# AC-DC.net
KiCad netlist of a schematic drawn in Altium Designer
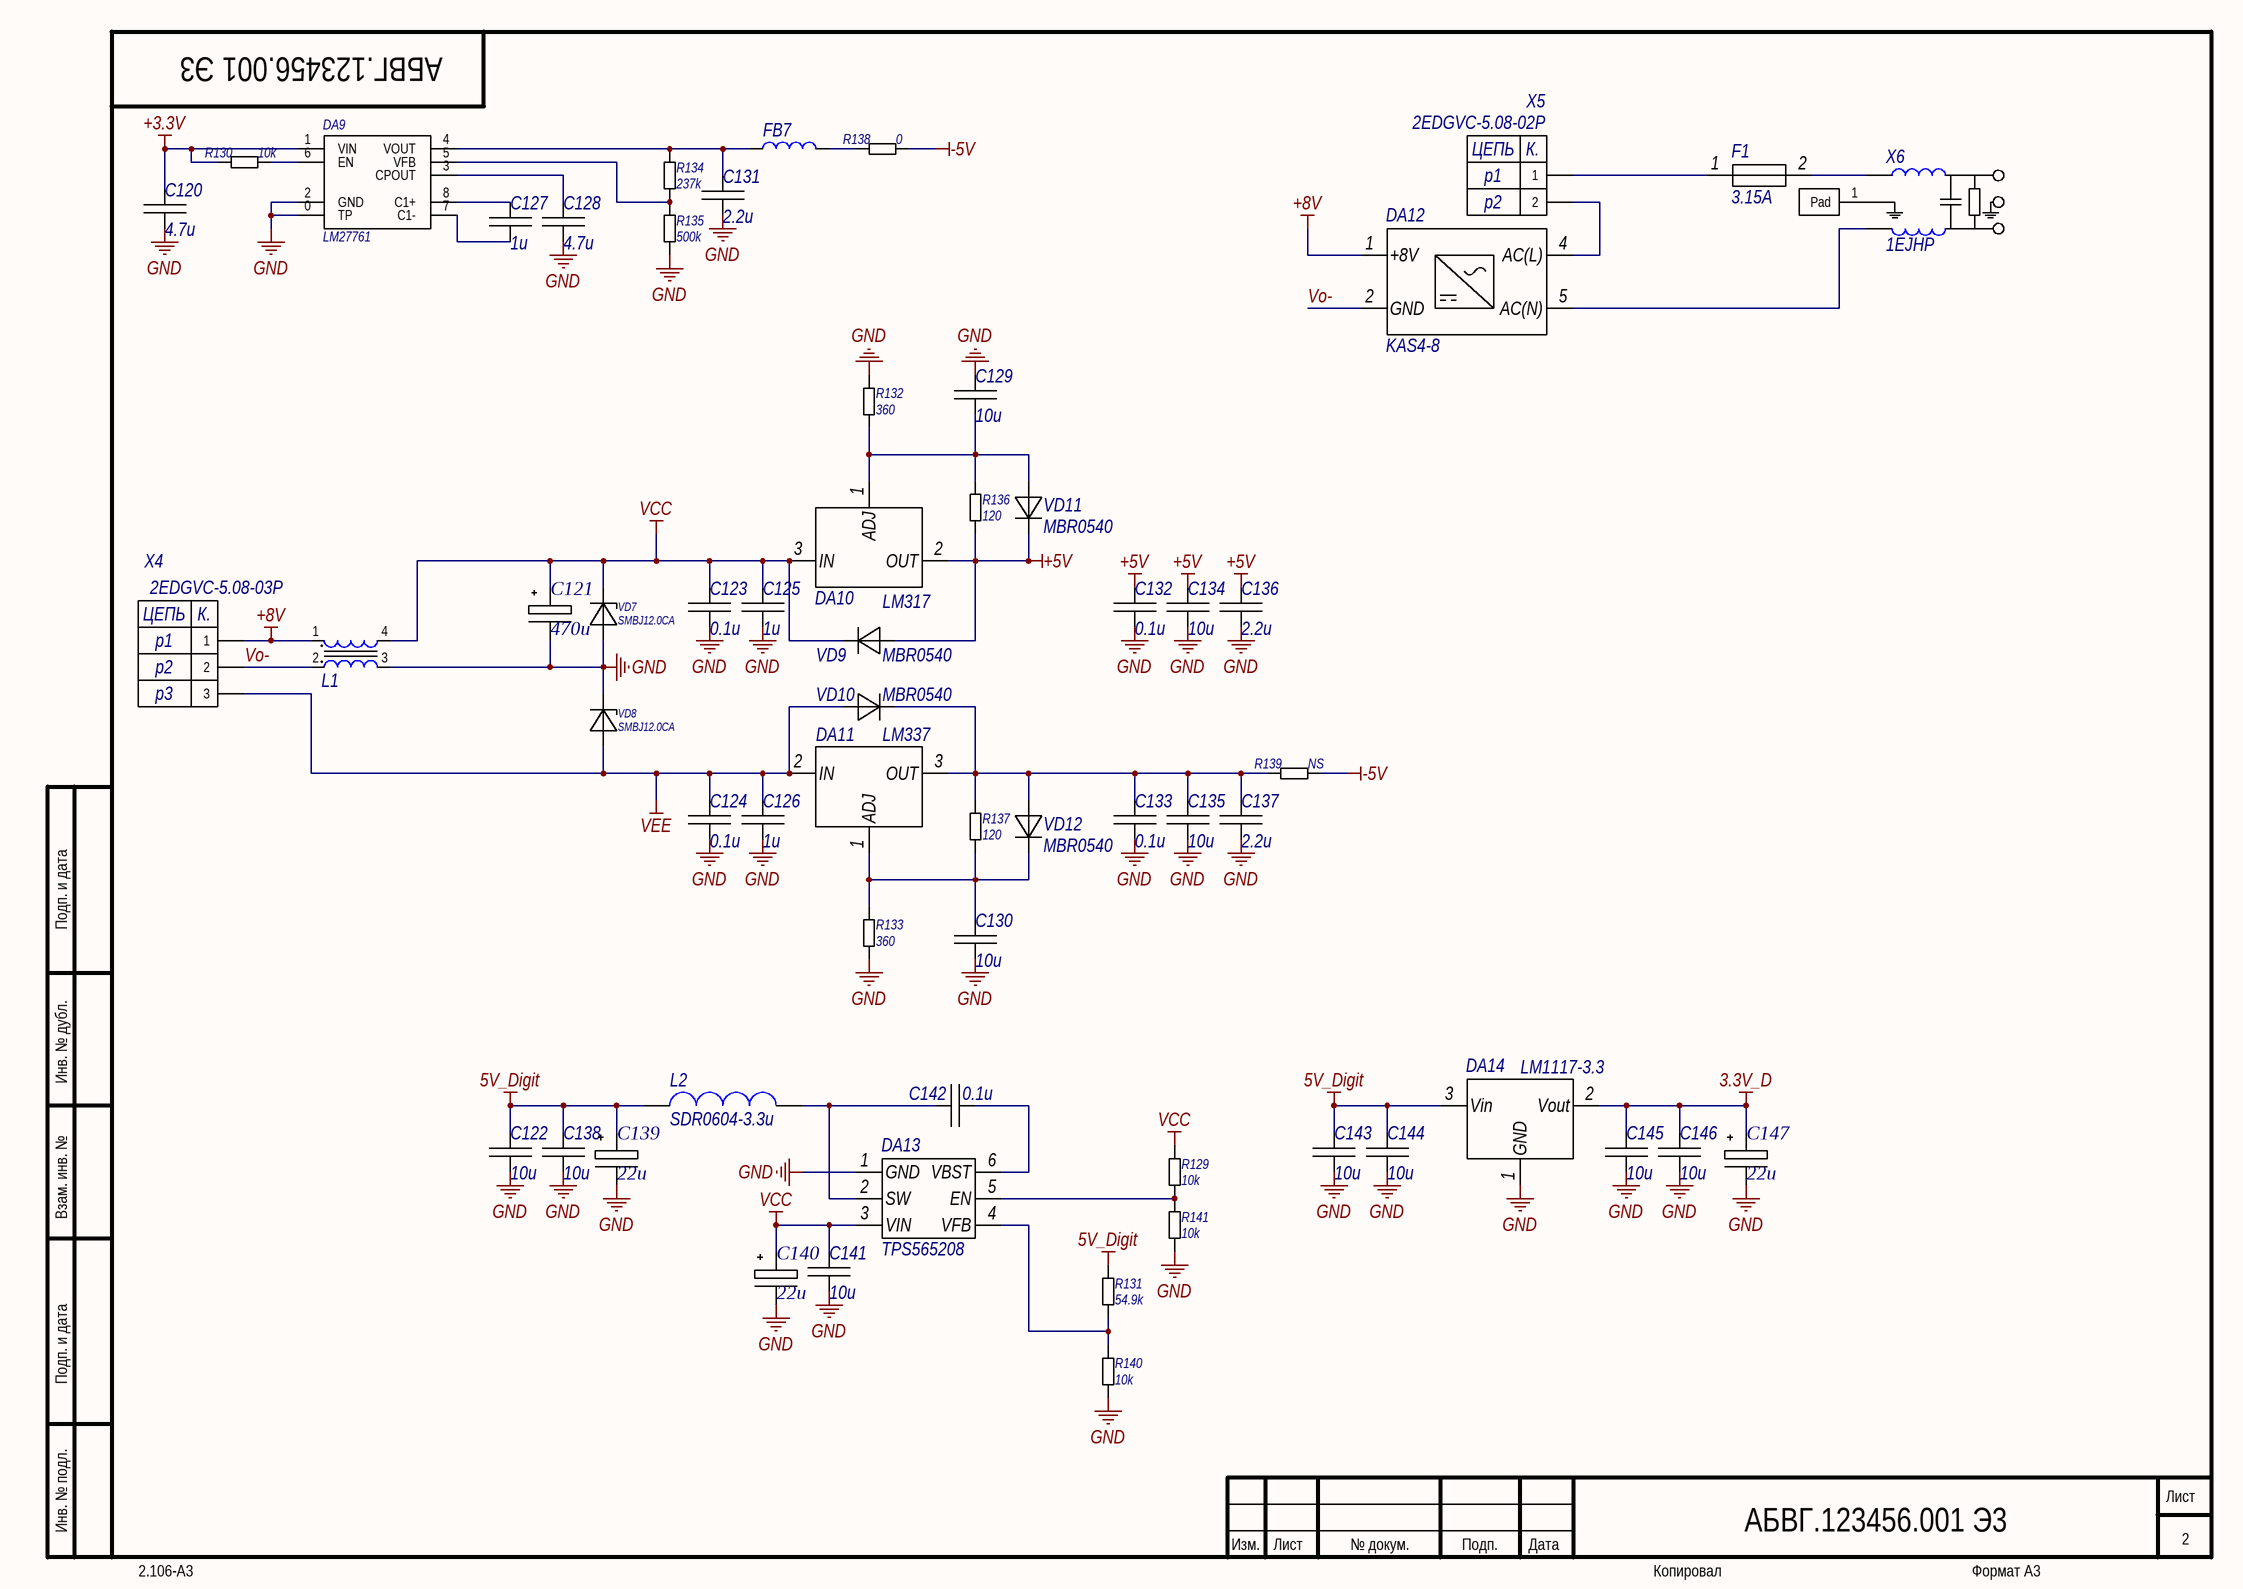
[diagram p0: AC-DC.SchDoc]

(export (version "E")
  (design (tool "Eeschema 10.0.6"))
  (components
    (comp (ref "C120")
      (value "4.7u")
      (footprint "C0805")
      (libsource (lib "ComLib") (part "Capacitor Ceramic SMD"))
    )
    (comp (ref "C121")
      (value "470u")
      (footprint "C1717")
      (libsource (lib "ComLib") (part "Capacitor Electrolytic"))
    )
    (comp (ref "C122")
      (value "10u")
      (footprint "C1206")
      (libsource (lib "ComLib") (part "Capacitor Ceramic SMD"))
    )
    (comp (ref "C123")
      (value "0.1u")
      (footprint "C1206")
      (libsource (lib "ComLib") (part "Capacitor Ceramic SMD"))
    )
    (comp (ref "C124")
      (value "0.1u")
      (footprint "C1206")
      (libsource (lib "ComLib") (part "Capacitor Ceramic SMD"))
    )
    (comp (ref "C125")
      (value "1u")
      (footprint "C1206")
      (libsource (lib "ComLib") (part "Capacitor Ceramic SMD"))
    )
    (comp (ref "C126")
      (value "1u")
      (footprint "C1206")
      (libsource (lib "ComLib") (part "Capacitor Ceramic SMD"))
    )
    (comp (ref "C127")
      (value "1u")
      (footprint "C0805")
      (libsource (lib "ComLib") (part "Capacitor Ceramic SMD"))
    )
    (comp (ref "C128")
      (value "4.7u")
      (footprint "C0805")
      (libsource (lib "ComLib") (part "Capacitor Ceramic SMD"))
    )
    (comp (ref "C129")
      (value "10u")
      (footprint "C1206")
      (libsource (lib "ComLib") (part "Capacitor Ceramic SMD"))
    )
    (comp (ref "C130")
      (value "10u")
      (footprint "C1206")
      (libsource (lib "ComLib") (part "Capacitor Ceramic SMD"))
    )
    (comp (ref "C131")
      (value "2.2u")
      (footprint "C0805")
      (libsource (lib "ComLib") (part "Capacitor Ceramic SMD"))
    )
    (comp (ref "C132")
      (value "0.1u")
      (footprint "C1206")
      (libsource (lib "ComLib") (part "Capacitor Ceramic SMD"))
    )
    (comp (ref "C133")
      (value "0.1u")
      (footprint "C1206")
      (libsource (lib "ComLib") (part "Capacitor Ceramic SMD"))
    )
    (comp (ref "C134")
      (value "10u")
      (footprint "C1206")
      (libsource (lib "ComLib") (part "Capacitor Ceramic SMD"))
    )
    (comp (ref "C135")
      (value "10u")
      (footprint "C1206")
      (libsource (lib "ComLib") (part "Capacitor Ceramic SMD"))
    )
    (comp (ref "C136")
      (value "2.2u")
      (footprint "C1206")
      (libsource (lib "ComLib") (part "Capacitor Ceramic SMD"))
    )
    (comp (ref "C137")
      (value "2.2u")
      (footprint "C1206")
      (libsource (lib "ComLib") (part "Capacitor Ceramic SMD"))
    )
    (comp (ref "C138")
      (value "10u")
      (footprint "C1206")
      (libsource (lib "ComLib") (part "Capacitor Ceramic SMD"))
    )
    (comp (ref "C139")
      (value "22u")
      (footprint "C0605")
      (libsource (lib "ComLib") (part "Capacitor Electrolytic"))
    )
    (comp (ref "C140")
      (value "22u")
      (footprint "C0605")
      (libsource (lib "ComLib") (part "Capacitor Electrolytic"))
    )
    (comp (ref "C141")
      (value "10u")
      (footprint "C1206")
      (libsource (lib "ComLib") (part "Capacitor Ceramic SMD"))
    )
    (comp (ref "C142")
      (value "0.1u")
      (footprint "C1206")
      (libsource (lib "ComLib") (part "Capacitor Ceramic SMD"))
    )
    (comp (ref "C143")
      (value "10u")
      (footprint "C1206")
      (libsource (lib "ComLib") (part "Capacitor Ceramic SMD"))
    )
    (comp (ref "C144")
      (value "10u")
      (footprint "C1206")
      (libsource (lib "ComLib") (part "Capacitor Ceramic SMD"))
    )
    (comp (ref "C145")
      (value "10u")
      (footprint "C1206")
      (libsource (lib "ComLib") (part "Capacitor Ceramic SMD"))
    )
    (comp (ref "C146")
      (value "10u")
      (footprint "C1206")
      (libsource (lib "ComLib") (part "Capacitor Ceramic SMD"))
    )
    (comp (ref "C147")
      (value "22u")
      (footprint "C0605")
      (libsource (lib "ComLib") (part "Capacitor Electrolytic"))
    )
    (comp (ref "DA9") (value "LM27761") (footprint "WSON-8") (libsource (lib "ComLib") (part "LM27761")))
    (comp (ref "DA10") (value "LM317") (footprint "D2PAK") (libsource (lib "Librio_TS") (part "LM317")))
    (comp (ref "DA11") (value "LM337") (footprint "D2PAK") (libsource (lib "Librio_TS") (part "LM337")))
    (comp (ref "DA12") (value "KAS4-8") (footprint "KAS4-8") (libsource (lib "ComLib") (part "KAS4-8")))
    (comp (ref "DA13")
      (value "TPS565208")
      (footprint "SOT23-6")
      (libsource (lib "ComLib") (part "TPS565208"))
    )
    (comp (ref "DA14")
      (value "LM1117-3.3")
      (footprint "DPAK - LM1117")
      (libsource (lib "Librio_TS") (part "LM1117"))
    )
    (comp (ref "F1") (value "3.15A") (footprint "5x20mm") (libsource (lib "ComLib") (part "FUSE_HOLDER")))
    (comp (ref "FB7")
      (value "MH1608-601Y")
      (footprint "L0603")
      (libsource (lib "ComLib") (part "Ferrite Bead"))
    )
    (comp (ref "L1")
      (value "744221")
      (footprint "WE-SL2 SMD")
      (libsource (lib "ComLib") (part "CommonModeChoke"))
    )
    (comp (ref "L2")
      (value "SDR0604-3.3u")
      (footprint "SDR0604")
      (libsource (lib "Librio_TS") (part "SDR0604"))
    )
    (comp (ref "P1") (value "PAD") (footprint "PAD") (libsource (lib "Librio_TS") (part "PAD")))
    (comp (ref "R129") (value "10k") (footprint "CR0805") (libsource (lib "ComLib") (part "Resistor SMD")))
    (comp (ref "R130") (value "10k") (footprint "CR0805") (libsource (lib "ComLib") (part "Resistor SMD")))
    (comp (ref "R131") (value "54.9k") (footprint "CR0805") (libsource (lib "ComLib") (part "Resistor SMD")))
    (comp (ref "R132") (value "360") (footprint "CR1206") (libsource (lib "ComLib") (part "Resistor SMD")))
    (comp (ref "R133") (value "360") (footprint "CR1206") (libsource (lib "ComLib") (part "Resistor SMD")))
    (comp (ref "R134") (value "237k") (footprint "CR0805") (libsource (lib "ComLib") (part "Resistor SMD")))
    (comp (ref "R135") (value "500k") (footprint "CR0805") (libsource (lib "ComLib") (part "Resistor SMD")))
    (comp (ref "R136") (value "120") (footprint "CR1206") (libsource (lib "ComLib") (part "Resistor SMD")))
    (comp (ref "R137") (value "120") (footprint "CR1206") (libsource (lib "ComLib") (part "Resistor SMD")))
    (comp (ref "R138") (value "0") (footprint "CR0805") (libsource (lib "ComLib") (part "Resistor SMD")))
    (comp (ref "R139") (value "NS") (footprint "CR0805") (libsource (lib "ComLib") (part "Resistor SMD")))
    (comp (ref "R140") (value "10k") (footprint "CR0805") (libsource (lib "ComLib") (part "Resistor SMD")))
    (comp (ref "R141") (value "10k") (footprint "CR0805") (libsource (lib "ComLib") (part "Resistor SMD")))
    (comp (ref "VD7")
      (value "SMBJ12.0CA")
      (footprint "DO-214AA")
      (libsource (lib "Librio_TS") (part "SMBJ5.0CA"))
    )
    (comp (ref "VD8")
      (value "SMBJ12.0CA")
      (footprint "DO-214AA")
      (libsource (lib "Librio_TS") (part "SMBJ5.0CA"))
    )
    (comp (ref "VD9") (value "MBR0540") (footprint "SOD123") (libsource (lib "ComLib") (part "Diode")))
    (comp (ref "VD10") (value "MBR0540") (footprint "SOD123") (libsource (lib "ComLib") (part "Diode")))
    (comp (ref "VD11") (value "MBR0540") (footprint "SOD123") (libsource (lib "ComLib") (part "Diode")))
    (comp (ref "VD12") (value "MBR0540") (footprint "SOD123") (libsource (lib "ComLib") (part "Diode")))
    (comp (ref "X4")
      (value "2EDGVC-5.08-03P")
      (footprint "2EDGVC-5.08-03P")
      (fields
        (field (name "ALTIUM_UNNAMED_1") "p1")
        (field (name "ALTIUM_UNNAMED_2") "p2")
        (field (name "ALTIUM_UNNAMED_3") "p3")
      )
      (libsource (lib "ComLib") (part "2EDGVC-5.08-03P"))
    )
    (comp (ref "X5")
      (value "2EDGVC-5.08-02P")
      (footprint "2EDGVC-5.08-02P")
      (fields (field (name "ALTIUM_UNNAMED_1") "p1") (field (name "ALTIUM_UNNAMED_2") "p2"))
      (libsource (lib "ComLib") (part "2EDGVC-5.08-02P"))
    )
    (comp (ref "X6") (value "1EJHP") (footprint "1EJHP") (libsource (lib "ComLib") (part "1EJHP")))
  )
  (nets
    (net (code "1") (name "+3.3V") (class "Default")
      (node (ref "C120") (pin "1") (pinfunction "1_1") (pintype "passive"))
      (node (ref "DA9") (pin "1") (pinfunction "VIN_1") (pintype "passive"))
      (node (ref "R130") (pin "2") (pintype "passive"))
    )
    (net (code "2") (name "+5V") (class "Default")
      (node (ref "C132") (pin "1") (pinfunction "1_1") (pintype "passive"))
      (node (ref "C134") (pin "1") (pinfunction "1_1") (pintype "passive"))
      (node (ref "C136") (pin "1") (pinfunction "1_1") (pintype "passive"))
      (node (ref "DA10") (pin "2") (pinfunction "OUT_2") (pintype "passive"))
      (node (ref "R136") (pin "1") (pintype "passive"))
      (node (ref "VD11") (pin "1") (pinfunction "1_1") (pintype "passive"))
      (node (ref "VD9") (pin "2") (pinfunction "2_2") (pintype "passive"))
    )
    (net (code "3") (name "+8V") (class "Default")
      (node (ref "DA12") (pin "1") (pinfunction "+8V_1") (pintype "passive"))
      (node (ref "L1") (pin "1") (pinfunction "1_1") (pintype "passive"))
      (node (ref "X4") (pin "1") (pinfunction "1_1") (pintype "passive"))
    )
    (net (code "4") (name "-5V") (class "Default")
      (node (ref "R138") (pin "1") (pintype "passive"))
      (node (ref "R139") (pin "1") (pintype "passive"))
    )
    (net (code "5") (name "/Vo-") (class "Default")
      (node (ref "DA12") (pin "2") (pinfunction "GND_2") (pintype "passive"))
      (node (ref "L1") (pin "2") (pinfunction "2_2") (pintype "passive"))
      (node (ref "X4") (pin "2") (pinfunction "2_2") (pintype "passive"))
    )
    (net (code "6") (name "3.3V_D") (class "Default")
      (node (ref "C145") (pin "1") (pinfunction "1_1") (pintype "passive"))
      (node (ref "C146") (pin "1") (pinfunction "1_1") (pintype "passive"))
      (node (ref "C147") (pin "1") (pinfunction "1_1") (pintype "passive"))
      (node (ref "DA14") (pin "2") (pinfunction "Vout_2") (pintype "passive"))
    )
    (net (code "7") (name "5V_Digit") (class "Default")
      (node (ref "C122") (pin "1") (pinfunction "1_1") (pintype "passive"))
      (node (ref "C138") (pin "1") (pinfunction "1_1") (pintype "passive"))
      (node (ref "C139") (pin "1") (pinfunction "1_1") (pintype "passive"))
      (node (ref "C143") (pin "1") (pinfunction "1_1") (pintype "passive"))
      (node (ref "C144") (pin "1") (pinfunction "1_1") (pintype "passive"))
      (node (ref "DA14") (pin "3") (pinfunction "Vin_3") (pintype "passive"))
      (node (ref "L2") (pin "1") (pinfunction "1_1") (pintype "passive"))
      (node (ref "R131") (pin "1") (pintype "passive"))
    )
    (net (code "8") (name "GND") (class "Default")
      (node (ref "C120") (pin "2") (pinfunction "2_2") (pintype "passive"))
      (node (ref "C121") (pin "2") (pinfunction "2_2") (pintype "passive"))
      (node (ref "C122") (pin "2") (pinfunction "2_2") (pintype "passive"))
      (node (ref "C123") (pin "2") (pinfunction "2_2") (pintype "passive"))
      (node (ref "C124") (pin "2") (pinfunction "2_2") (pintype "passive"))
      (node (ref "C125") (pin "2") (pinfunction "2_2") (pintype "passive"))
      (node (ref "C126") (pin "2") (pinfunction "2_2") (pintype "passive"))
      (node (ref "C128") (pin "2") (pinfunction "2_2") (pintype "passive"))
      (node (ref "C129") (pin "1") (pinfunction "1_1") (pintype "passive"))
      (node (ref "C130") (pin "2") (pinfunction "2_2") (pintype "passive"))
      (node (ref "C131") (pin "2") (pinfunction "2_2") (pintype "passive"))
      (node (ref "C132") (pin "2") (pinfunction "2_2") (pintype "passive"))
      (node (ref "C133") (pin "2") (pinfunction "2_2") (pintype "passive"))
      (node (ref "C134") (pin "2") (pinfunction "2_2") (pintype "passive"))
      (node (ref "C135") (pin "2") (pinfunction "2_2") (pintype "passive"))
      (node (ref "C136") (pin "2") (pinfunction "2_2") (pintype "passive"))
      (node (ref "C137") (pin "2") (pinfunction "2_2") (pintype "passive"))
      (node (ref "C138") (pin "2") (pinfunction "2_2") (pintype "passive"))
      (node (ref "C139") (pin "2") (pinfunction "2_2") (pintype "passive"))
      (node (ref "C140") (pin "2") (pinfunction "2_2") (pintype "passive"))
      (node (ref "C141") (pin "2") (pinfunction "2_2") (pintype "passive"))
      (node (ref "C143") (pin "2") (pinfunction "2_2") (pintype "passive"))
      (node (ref "C144") (pin "2") (pinfunction "2_2") (pintype "passive"))
      (node (ref "C145") (pin "2") (pinfunction "2_2") (pintype "passive"))
      (node (ref "C146") (pin "2") (pinfunction "2_2") (pintype "passive"))
      (node (ref "C147") (pin "2") (pinfunction "2_2") (pintype "passive"))
      (node (ref "DA13") (pin "1") (pinfunction "GND_1") (pintype "passive"))
      (node (ref "DA14") (pin "1") (pinfunction "GND_1") (pintype "passive"))
      (node (ref "DA9") (pin "0") (pinfunction "TP_0") (pintype "passive"))
      (node (ref "DA9") (pin "2") (pinfunction "GND_2") (pintype "passive"))
      (node (ref "L1") (pin "3") (pinfunction "3_3") (pintype "passive"))
      (node (ref "R132") (pin "2") (pintype "passive"))
      (node (ref "R133") (pin "1") (pintype "passive"))
      (node (ref "R135") (pin "1") (pintype "passive"))
      (node (ref "R140") (pin "2") (pintype "passive"))
      (node (ref "R141") (pin "2") (pintype "passive"))
      (node (ref "VD7") (pin "2") (pinfunction "2_2") (pintype "passive"))
      (node (ref "VD8") (pin "1") (pinfunction "1_1") (pintype "passive"))
    )
    (net (code "9") (name "Net-(DA9-C1+)") (class "Default")
      (node (ref "C127") (pin "1") (pinfunction "1_1") (pintype "passive"))
      (node (ref "DA9") (pin "8") (pinfunction "C1+_8") (pintype "passive"))
    )
    (net (code "10") (name "Net-(DA9-C1-)") (class "Default")
      (node (ref "C127") (pin "2") (pinfunction "2_2") (pintype "passive"))
      (node (ref "DA9") (pin "7") (pinfunction "C1-_7") (pintype "passive"))
    )
    (net (code "11") (name "Net-(DA9-CPOUT)") (class "Default")
      (node (ref "C128") (pin "1") (pinfunction "1_1") (pintype "passive"))
      (node (ref "DA9") (pin "3") (pinfunction "CPOUT_3") (pintype "passive"))
    )
    (net (code "12") (name "Net-(DA9-EN)") (class "Default")
      (node (ref "DA9") (pin "6") (pinfunction "EN_6") (pintype "passive"))
      (node (ref "R130") (pin "1") (pintype "passive"))
    )
    (net (code "13") (name "Net-(DA9-VFB)") (class "Default")
      (node (ref "DA9") (pin "5") (pinfunction "VFB_5") (pintype "passive"))
      (node (ref "R134") (pin "1") (pintype "passive"))
      (node (ref "R135") (pin "2") (pintype "passive"))
    )
    (net (code "14") (name "Net-(DA9-VOUT)") (class "Default")
      (node (ref "C131") (pin "1") (pinfunction "1_1") (pintype "passive"))
      (node (ref "DA9") (pin "4") (pinfunction "VOUT_4") (pintype "passive"))
      (node (ref "FB7") (pin "1") (pinfunction "1_1") (pintype "passive"))
      (node (ref "R134") (pin "2") (pintype "passive"))
    )
    (net (code "15") (name "Net-(DA10-ADJ)") (class "Default")
      (node (ref "C129") (pin "2") (pinfunction "2_2") (pintype "passive"))
      (node (ref "DA10") (pin "1") (pinfunction "ADJ_1") (pintype "passive"))
      (node (ref "R132") (pin "1") (pintype "passive"))
      (node (ref "R136") (pin "2") (pintype "passive"))
      (node (ref "VD11") (pin "2") (pinfunction "2_2") (pintype "passive"))
    )
    (net (code "16") (name "Net-(DA11-ADJ)") (class "Default")
      (node (ref "C130") (pin "1") (pinfunction "1_1") (pintype "passive"))
      (node (ref "DA11") (pin "1") (pinfunction "ADJ_1") (pintype "passive"))
      (node (ref "R133") (pin "2") (pintype "passive"))
      (node (ref "R137") (pin "1") (pintype "passive"))
      (node (ref "VD12") (pin "1") (pinfunction "1_1") (pintype "passive"))
    )
    (net (code "17") (name "Net-(DA11-OUT)") (class "Default")
      (node (ref "C133") (pin "1") (pinfunction "1_1") (pintype "passive"))
      (node (ref "C135") (pin "1") (pinfunction "1_1") (pintype "passive"))
      (node (ref "C137") (pin "1") (pinfunction "1_1") (pintype "passive"))
      (node (ref "DA11") (pin "3") (pinfunction "OUT_3") (pintype "passive"))
      (node (ref "R137") (pin "2") (pintype "passive"))
      (node (ref "R139") (pin "2") (pintype "passive"))
      (node (ref "VD10") (pin "1") (pinfunction "1_1") (pintype "passive"))
      (node (ref "VD12") (pin "2") (pinfunction "2_2") (pintype "passive"))
    )
    (net (code "18") (name "Net-(DA12-AC(L))") (class "Default")
      (node (ref "DA12") (pin "4") (pinfunction "AC(L)_4") (pintype "passive"))
      (node (ref "X5") (pin "2") (pinfunction "2_2") (pintype "passive"))
    )
    (net (code "19") (name "Net-(DA12-AC(N))") (class "Default")
      (node (ref "DA12") (pin "5") (pinfunction "AC(N)_5") (pintype "passive"))
      (node (ref "X6") (pin "2") (pinfunction "AC(N)_2") (pintype "passive"))
    )
    (net (code "20") (name "Net-(DA13-EN)") (class "Default")
      (node (ref "DA13") (pin "5") (pinfunction "EN_5") (pintype "passive"))
      (node (ref "R129") (pin "2") (pintype "passive"))
      (node (ref "R141") (pin "1") (pintype "passive"))
    )
    (net (code "21") (name "Net-(DA13-SW)") (class "Default")
      (node (ref "C142") (pin "1") (pinfunction "1_1") (pintype "passive"))
      (node (ref "DA13") (pin "2") (pinfunction "SW_2") (pintype "passive"))
      (node (ref "L2") (pin "2") (pinfunction "2_2") (pintype "passive"))
    )
    (net (code "22") (name "Net-(DA13-VBST)") (class "Default")
      (node (ref "C142") (pin "2") (pinfunction "2_2") (pintype "passive"))
      (node (ref "DA13") (pin "6") (pinfunction "VBST_6") (pintype "passive"))
    )
    (net (code "23") (name "Net-(DA13-VFB)") (class "Default")
      (node (ref "DA13") (pin "4") (pinfunction "VFB_4") (pintype "passive"))
      (node (ref "R131") (pin "2") (pintype "passive"))
      (node (ref "R140") (pin "1") (pintype "passive"))
    )
    (net (code "24") (name "Net-(F1-IN)") (class "Default")
      (node (ref "F1") (pin "1") (pinfunction "IN_1") (pintype "passive"))
      (node (ref "X5") (pin "1") (pinfunction "1_1") (pintype "passive"))
    )
    (net (code "25") (name "Net-(F1-OUT)") (class "Default")
      (node (ref "F1") (pin "2") (pinfunction "OUT_2") (pintype "passive"))
      (node (ref "X6") (pin "1") (pinfunction "AC(L)_1") (pintype "passive"))
    )
    (net (code "26") (name "Net-(FB7-Pad2)") (class "Default")
      (node (ref "FB7") (pin "2") (pinfunction "2_2") (pintype "passive"))
      (node (ref "R138") (pin "2") (pintype "passive"))
    )
    (net (code "27") (name "Net-(X6-G)") (class "Default")
      (node (ref "P1") (pin "1") (pinfunction "Pad_1") (pintype "passive"))
      (node (ref "X6") (pin "3") (pinfunction "G_3") (pintype "passive"))
    )
    (net (code "28") (name "VCC") (class "Default")
      (node (ref "C121") (pin "1") (pinfunction "1_1") (pintype "passive"))
      (node (ref "C123") (pin "1") (pinfunction "1_1") (pintype "passive"))
      (node (ref "C125") (pin "1") (pinfunction "1_1") (pintype "passive"))
      (node (ref "C140") (pin "1") (pinfunction "1_1") (pintype "passive"))
      (node (ref "C141") (pin "1") (pinfunction "1_1") (pintype "passive"))
      (node (ref "DA10") (pin "3") (pinfunction "IN_3") (pintype "passive"))
      (node (ref "DA13") (pin "3") (pinfunction "VIN_3") (pintype "passive"))
      (node (ref "L1") (pin "4") (pinfunction "4_4") (pintype "passive"))
      (node (ref "R129") (pin "1") (pintype "passive"))
      (node (ref "VD7") (pin "1") (pinfunction "1_1") (pintype "passive"))
      (node (ref "VD9") (pin "1") (pinfunction "1_1") (pintype "passive"))
    )
    (net (code "29") (name "VEE") (class "Default")
      (node (ref "C124") (pin "1") (pinfunction "1_1") (pintype "passive"))
      (node (ref "C126") (pin "1") (pinfunction "1_1") (pintype "passive"))
      (node (ref "DA11") (pin "2") (pinfunction "IN_2") (pintype "passive"))
      (node (ref "VD10") (pin "2") (pinfunction "2_2") (pintype "passive"))
      (node (ref "VD8") (pin "2") (pinfunction "2_2") (pintype "passive"))
      (node (ref "X4") (pin "3") (pinfunction "3_3") (pintype "passive"))
    )
    (net (code "30") (name "unconnected-(DA12-NC-Pad3)") (class "Default")
      (node (ref "DA12") (pin "3") (pinfunction "NC_3") (pintype "passive"))
    )
    (net (code "31") (name "unconnected-(DA12-NC-Pad6)") (class "Default")
      (node (ref "DA12") (pin "6") (pinfunction "NC_6") (pintype "passive"))
    )
  )
)
